# PowerModule.net
KiCad netlist of a schematic drawn in EAGLE
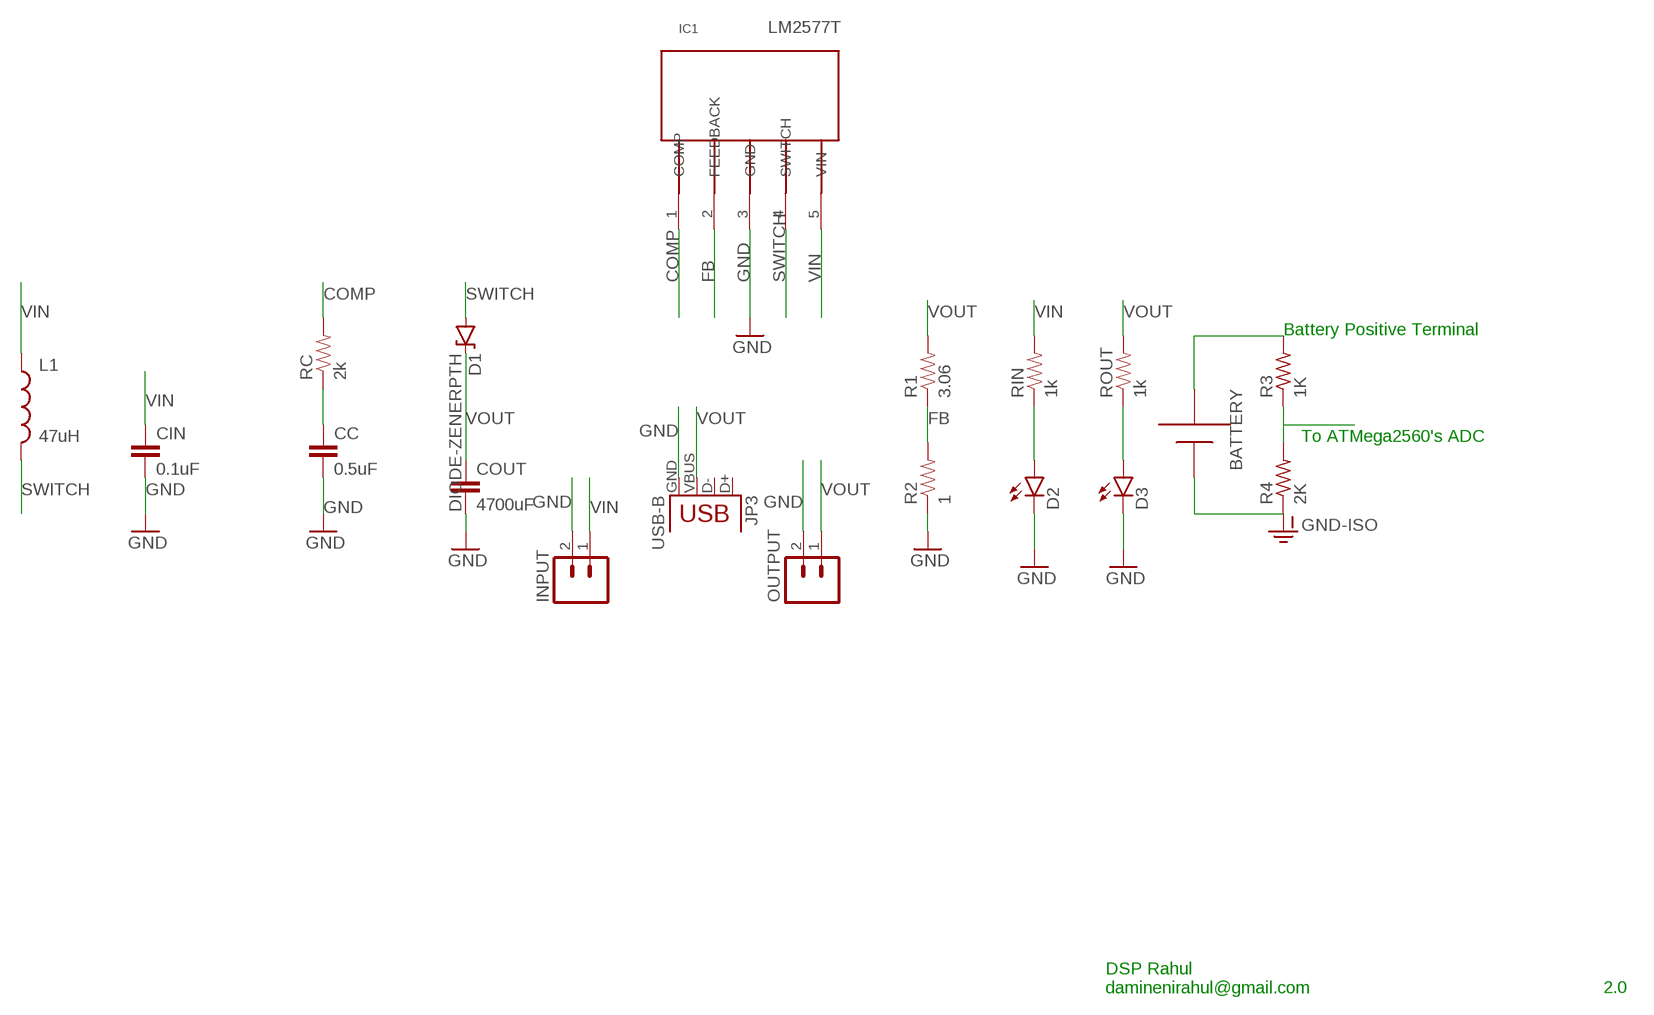
[diagram p0: schematic, sheet 1]

(export (version "E")
  (design (tool "Eeschema 10.0.6"))
  (components
    (comp (ref "BATTERY")
      (value "4.1V ~ 3.7V")
      (footprint "eagle-import:12BH412")
      (libsource (lib "eagle-import") (part "AAA"))
    )
    (comp (ref "CC")
      (value "0.5uF")
      (footprint "eagle-import:CAP-PTH-SMALLEZ")
      (libsource (lib "eagle-import") (part "CAPEZ"))
    )
    (comp (ref "CIN")
      (value "0.1uF")
      (footprint "eagle-import:CAP-PTH-SMALL")
      (libsource (lib "eagle-import") (part "CAPPTH"))
    )
    (comp (ref "COUT")
      (value "4700uF")
      (footprint "eagle-import:CAP-PTH-LARGE")
      (libsource (lib "eagle-import") (part "CAPPTH3"))
    )
    (comp (ref "D1")
      (value "DIODE-ZENERPTH")
      (footprint "eagle-import:DIODE-ZENER")
      (libsource (lib "eagle-import") (part "DIODE-ZENERPTH"))
    )
    (comp (ref "D2")
      (value "LED5MM-KIT")
      (footprint "eagle-import:LED5MM-KIT")
      (libsource (lib "eagle-import") (part "LED5MM-KIT"))
    )
    (comp (ref "D3")
      (value "LED5MM-KIT")
      (footprint "eagle-import:LED5MM-KIT")
      (libsource (lib "eagle-import") (part "LED5MM-KIT"))
    )
    (comp (ref "IC1")
      (value "LM2577T")
      (footprint "eagle-import:TO220-5")
      (libsource (lib "eagle-import") (part "LM2577T"))
    )
    (comp (ref "INPUT")
      (value "M02POLAR_LOCK")
      (footprint "eagle-import:MOLEX-1X2_LOCK")
      (libsource (lib "eagle-import") (part "M02POLAR_LOCK"))
    )
    (comp (ref "JP3")
      (value "USB-B")
      (footprint "eagle-import:USB-B-PTH")
      (libsource (lib "eagle-import") (part "USBPTH"))
    )
    (comp (ref "L1")
      (value "47uH")
      (footprint "eagle-import:RLB0912")
      (libsource (lib "eagle-import") (part "INDUCTORRLB0912"))
    )
    (comp (ref "OUTPUT")
      (value "M02POLAR_LOCK")
      (footprint "eagle-import:MOLEX-1X2_LOCK")
      (libsource (lib "eagle-import") (part "M02POLAR_LOCK"))
    )
    (comp (ref "R1")
      (value "3.06")
      (footprint "eagle-import:AXIAL-0.3EZ")
      (libsource (lib "eagle-import") (part "RESISTOREZ"))
    )
    (comp (ref "R2")
      (value "1")
      (footprint "eagle-import:AXIAL-0.3EZ")
      (libsource (lib "eagle-import") (part "RESISTOREZ"))
    )
    (comp (ref "R3")
      (value "1K")
      (footprint "eagle-import:0207_9")
      (libsource (lib "eagle-import") (part "R-US_0207/9"))
    )
    (comp (ref "R4")
      (value "2K")
      (footprint "eagle-import:0207_9")
      (libsource (lib "eagle-import") (part "R-US_0207/9"))
    )
    (comp (ref "RC")
      (value "2k")
      (footprint "eagle-import:AXIAL-0.3EZ")
      (libsource (lib "eagle-import") (part "RESISTOREZ"))
    )
    (comp (ref "RIN")
      (value "1k")
      (footprint "eagle-import:AXIAL-0.3EZ")
      (libsource (lib "eagle-import") (part "RESISTOREZ"))
    )
    (comp (ref "ROUT")
      (value "1k")
      (footprint "eagle-import:AXIAL-0.3EZ")
      (libsource (lib "eagle-import") (part "RESISTOREZ"))
    )
  )
  (nets
    (net (code "1") (name "/COMP") (class "Default")
      (node (ref "IC1") (pin "1") (pinfunction "COMP_1") (pintype "input"))
      (node (ref "RC") (pin "P$2") (pinfunction "2_P$2") (pintype "passive"))
    )
    (net (code "2") (name "/FB") (class "Default")
      (node (ref "IC1") (pin "2") (pinfunction "FEEDBACK_2") (pintype "input"))
      (node (ref "R1") (pin "P$1") (pinfunction "1_P$1") (pintype "passive"))
      (node (ref "R2") (pin "P$2") (pinfunction "2_P$2") (pintype "passive"))
    )
    (net (code "3") (name "/SWITCH") (class "Default")
      (node (ref "D1") (pin "P$2") (pinfunction "A_P$2") (pintype "passive"))
      (node (ref "IC1") (pin "4") (pinfunction "SWITCH_4") (pintype "power_in"))
      (node (ref "L1") (pin "2") (pinfunction "2_2") (pintype "passive"))
    )
    (net (code "4") (name "/VIN") (class "Default")
      (node (ref "CIN") (pin "1") (pinfunction "1_1") (pintype "passive"))
      (node (ref "IC1") (pin "5") (pinfunction "VIN_5") (pintype "input"))
      (node (ref "INPUT") (pin "1") (pinfunction "1_1") (pintype "passive"))
      (node (ref "L1") (pin "1") (pinfunction "1_1") (pintype "passive"))
      (node (ref "RIN") (pin "P$2") (pinfunction "2_P$2") (pintype "passive"))
    )
    (net (code "5") (name "/VOUT") (class "Default")
      (node (ref "COUT") (pin "1") (pinfunction "1_1") (pintype "passive"))
      (node (ref "D1") (pin "P$1") (pinfunction "C_P$1") (pintype "passive"))
      (node (ref "JP3") (pin "VBUS") (pinfunction "VBUS_VBUS") (pintype "bidirectional"))
      (node (ref "OUTPUT") (pin "1") (pinfunction "1_1") (pintype "passive"))
      (node (ref "R1") (pin "P$2") (pinfunction "2_P$2") (pintype "passive"))
      (node (ref "ROUT") (pin "P$2") (pinfunction "2_P$2") (pintype "passive"))
    )
    (net (code "6") (name "GND") (class "Default")
      (node (ref "CC") (pin "2") (pinfunction "2_2") (pintype "passive"))
      (node (ref "CIN") (pin "2") (pinfunction "2_2") (pintype "passive"))
      (node (ref "COUT") (pin "2") (pinfunction "2_2") (pintype "passive"))
      (node (ref "D2") (pin "K") (pinfunction "C_K") (pintype "passive"))
      (node (ref "D3") (pin "K") (pinfunction "C_K") (pintype "passive"))
      (node (ref "IC1") (pin "3") (pinfunction "GND_3") (pintype "power_in"))
      (node (ref "INPUT") (pin "2") (pinfunction "2_2") (pintype "passive"))
      (node (ref "JP3") (pin "GND") (pinfunction "GND_GND") (pintype "bidirectional"))
      (node (ref "OUTPUT") (pin "2") (pinfunction "2_2") (pintype "passive"))
      (node (ref "R2") (pin "P$1") (pinfunction "1_P$1") (pintype "passive"))
    )
    (net (code "7") (name "GND-ISO") (class "Default")
      (node (ref "BATTERY") (pin "+") (pinfunction "+_+") (pintype "bidirectional"))
      (node (ref "R4") (pin "1") (pinfunction "1_1") (pintype "passive"))
    )
    (net (code "8") (name "Net-(BATTERY-Pad-)") (class "Default")
      (node (ref "BATTERY") (pin "-") (pinfunction "-_-") (pintype "bidirectional"))
      (node (ref "R3") (pin "2") (pinfunction "2_2") (pintype "passive"))
    )
    (net (code "9") (name "Net-(R3-Pad1)") (class "Default")
      (node (ref "R3") (pin "1") (pinfunction "1_1") (pintype "passive"))
      (node (ref "R4") (pin "2") (pinfunction "2_2") (pintype "passive"))
    )
    (net (code "10") (name "Net-(RC-1)") (class "Default")
      (node (ref "CC") (pin "1") (pinfunction "1_1") (pintype "passive"))
      (node (ref "RC") (pin "P$1") (pinfunction "1_P$1") (pintype "passive"))
    )
    (net (code "11") (name "Net-(RIN-1)") (class "Default")
      (node (ref "D2") (pin "A") (pinfunction "A_A") (pintype "passive"))
      (node (ref "RIN") (pin "P$1") (pinfunction "1_P$1") (pintype "passive"))
    )
    (net (code "12") (name "Net-(ROUT-1)") (class "Default")
      (node (ref "D3") (pin "A") (pinfunction "A_A") (pintype "passive"))
      (node (ref "ROUT") (pin "P$1") (pinfunction "1_P$1") (pintype "passive"))
    )
    (net (code "13") (name "unconnected-(JP3-PadD+)") (class "Default")
      (node (ref "JP3") (pin "D+") (pinfunction "D+_D+") (pintype "bidirectional"))
    )
    (net (code "14") (name "unconnected-(JP3-PadD-)") (class "Default")
      (node (ref "JP3") (pin "D-") (pinfunction "D-_D-") (pintype "bidirectional"))
    )
  )
)
